# wifi-usb-breakout.net
KiCad netlist of a schematic drawn in EAGLE
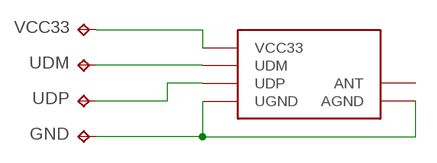
[diagram p0: schematic, sheet 1]

(export (version "E")
  (design (tool "Eeschema 10.0.6"))
  (components
    (comp (ref "GND")
      (value "TPTP09R")
      (footprint "eagle-import:TP09R")
      (libsource (lib "eagle-import") (part "TPTP09R"))
    )
    (comp (ref "U$1")
      (value "USB-WIFI-MODULE")
      (footprint "eagle-import:USB-WIFI-MODULE")
      (libsource (lib "eagle-import") (part "USB-WIFI-MODULE"))
    )
    (comp (ref "UDM")
      (value "TPTP09R")
      (footprint "eagle-import:TP09R")
      (libsource (lib "eagle-import") (part "TPTP09R"))
    )
    (comp (ref "UDP")
      (value "TPTP09R")
      (footprint "eagle-import:TP09R")
      (libsource (lib "eagle-import") (part "TPTP09R"))
    )
    (comp (ref "VCC33")
      (value "TPTP09R")
      (footprint "eagle-import:TP09R")
      (libsource (lib "eagle-import") (part "TPTP09R"))
    )
  )
  (nets
    (net (code "1") (name "Net-(U$1-AGND)") (class "Default")
      (node (ref "GND") (pin "TP") (pinfunction "TP_TP") (pintype "input"))
      (node (ref "U$1") (pin "P$4") (pinfunction "UGND_P$4") (pintype "bidirectional"))
      (node (ref "U$1") (pin "P$5") (pinfunction "AGND_P$5") (pintype "bidirectional"))
    )
    (net (code "2") (name "Net-(U$1-UDM)") (class "Default")
      (node (ref "U$1") (pin "P$2") (pinfunction "UDM_P$2") (pintype "bidirectional"))
      (node (ref "UDM") (pin "TP") (pinfunction "TP_TP") (pintype "input"))
    )
    (net (code "3") (name "Net-(U$1-UDP)") (class "Default")
      (node (ref "U$1") (pin "P$3") (pinfunction "UDP_P$3") (pintype "bidirectional"))
      (node (ref "UDP") (pin "TP") (pinfunction "TP_TP") (pintype "input"))
    )
    (net (code "4") (name "Net-(U$1-VCC33)") (class "Default")
      (node (ref "U$1") (pin "P$1") (pinfunction "VCC33_P$1") (pintype "bidirectional"))
      (node (ref "VCC33") (pin "TP") (pinfunction "TP_TP") (pintype "input"))
    )
    (net (code "5") (name "unconnected-(U$1-ANT-PadP$6)") (class "Default")
      (node (ref "U$1") (pin "P$6") (pinfunction "ANT_P$6") (pintype "bidirectional"))
    )
  )
)
